# schema.net
KiCad netlist of a schematic drawn in Altium Designer
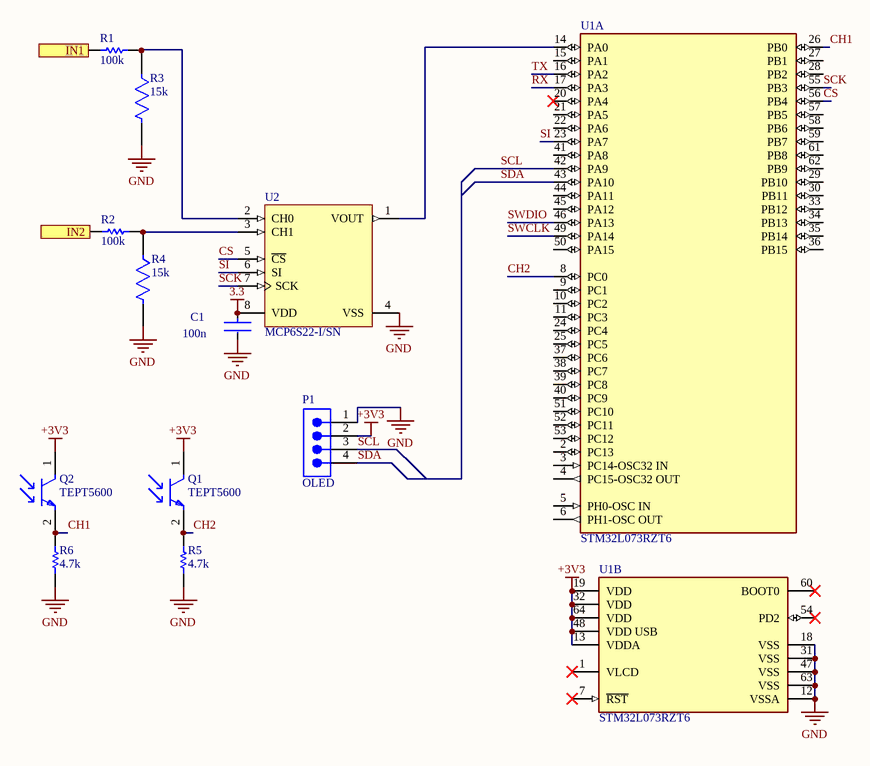
[diagram p0: schema.SchDoc]

(export (version "E")
  (design (tool "Eeschema 10.0.6"))
  (components
    (comp (ref "C1")
      (value "100n")
      (footprint "FP-0402B104K500CT-IPC_C")
      (description "CAP CER 0.1UF 50V X7R 0402")
      (fields (field (name "TOLERANCE") "10%"))
      (libsource (lib "Altium Content Vault") (part "11868f565c42a9108669ba33697ecf6"))
    )
    (comp (ref "P1")
      (value "OLED")
      (footprint "SMTC-MTSW-104-07-X-S-170")
      (fields (field (name "PARTNUMBER") "MTSW-104-07-T-S-170") (field (name "MANUFACTURER") "Samtec"))
      (libsource (lib "Altium Content Vault") (part "SMTC-MTSW-104-07-X-S-170"))
    )
    (comp (ref "Q1")
      (value "TEPT5600")
      (footprint "FP-6_544-5410_01-4-MFG")
      (description "VEMT2023SLX01 VEMT2023 Series 20 V 50 mA Silicon NPN Phototransistor - SMD-2")
      (libsource (lib "Altium Content Vault") (part "9aae5ca7057449e2492cc69ba8b14d6"))
    )
    (comp (ref "Q2")
      (value "TEPT5600")
      (footprint "FP-6_544-5410_01-4-MFG")
      (description "VEMT2023SLX01 VEMT2023 Series 20 V 50 mA Silicon NPN Phototransistor - SMD-2")
      (libsource (lib "Altium Content Vault") (part "9aae5ca7057449e2492cc69ba8b14d6"))
    )
    (comp (ref "R1")
      (value "100k")
      (footprint "RESC1005X40X25ML10T10")
      (fields (field (name "PART NUMBER") "SG73P1ETTP1003F") (field (name "MANUFACTURER") "KOA Speer"))
      (libsource (lib "Altium Content Vault") (part "RES"))
    )
    (comp (ref "R2")
      (value "100k")
      (footprint "RESC1005X40X25ML10T10")
      (fields (field (name "PART NUMBER") "SG73P1ETTP1003F") (field (name "MANUFACTURER") "KOA Speer"))
      (libsource (lib "Altium Content Vault") (part "RES"))
    )
    (comp (ref "R3")
      (value "15k")
      (footprint "FP-CRGP0603-IPC_C")
      (description "CRGP0603 15KΩ 0.25W ±100ppm/°C 1% 50V")
      (fields (field (name "MANUFACTURER") "TE") (field (name "MANUFACTURER PART NUMBER") "CRGP0603F15K"))
      (libsource (lib "Altium Content Vault") (part "1029c3af85768c4190bb7ad29bc67b5"))
    )
    (comp (ref "R4")
      (value "15k")
      (footprint "FP-CRGP0603-IPC_C")
      (description "CRGP0603 15KΩ 0.25W ±100ppm/°C 1% 50V")
      (fields (field (name "MANUFACTURER") "TE") (field (name "MANUFACTURER PART NUMBER") "CRGP0603F15K"))
      (libsource (lib "Altium Content Vault") (part "1029c3af85768c4190bb7ad29bc67b5"))
    )
    (comp (ref "R5")
      (value "4.7k")
      (footprint "RESC2512(6432)_N")
      (description "825R 1W 1% 2512 (6432 Metric)  SMD")
      (fields (field (name "POWER") "1 W") (field (name "TOLERANCE") "1 %"))
      (libsource (lib "Altium Content Vault") (part "RES"))
    )
    (comp (ref "R6")
      (value "4.7k")
      (footprint "RESC2512(6432)_N")
      (description "825R 1W 1% 2512 (6432 Metric)  SMD")
      (fields (field (name "POWER") "1 W") (field (name "TOLERANCE") "1 %"))
      (libsource (lib "Altium Content Vault") (part "RES"))
    )
    (comp (ref "U1")
      (value "STM32L073RZT6")
      (footprint "FP-LQFP64-5W-MFG")
      (description "IC MCU 32BIT 192KB FLASH 64LQFP")
      (libsource (lib "Altium Content Vault") (part "4466eda20ed5015702b21cb01f06cb7"))
    )
    (comp (ref "U2")
      (value "MCP6S22-I/SN")
      (footprint "SOIC-SN8_M")
      (libsource (lib "Altium Content Vault") (part "AMP-VGA-MCP6S22-IL8"))
    )
  )
  (nets
    (net (code "1") (name "+3V3") (class "Default")
      (node (ref "P1") (pin "2") (pinfunction "2_2") (pintype "passive"))
      (node (ref "Q1") (pin "1") (pinfunction "C_1") (pintype "passive"))
      (node (ref "Q2") (pin "1") (pinfunction "C_1") (pintype "passive"))
      (node (ref "U1") (pin "13") (pinfunction "VDDA_13") (pintype "power_in"))
      (node (ref "U1") (pin "19") (pinfunction "VDD_19") (pintype "power_in"))
      (node (ref "U1") (pin "32") (pinfunction "VDD_32") (pintype "power_in"))
      (node (ref "U1") (pin "48") (pinfunction "VDD_USB_48") (pintype "power_in"))
      (node (ref "U1") (pin "64") (pinfunction "VDD_64") (pintype "power_in"))
    )
    (net (code "2") (name "/CH1") (class "Default")
      (node (ref "Q2") (pin "2") (pinfunction "E_2") (pintype "passive"))
      (node (ref "R6") (pin "2") (pinfunction "2_2") (pintype "passive"))
      (node (ref "U1") (pin "26") (pinfunction "PB0_26") (pintype "bidirectional"))
    )
    (net (code "3") (name "/CH2") (class "Default")
      (node (ref "Q1") (pin "2") (pinfunction "E_2") (pintype "passive"))
      (node (ref "R5") (pin "2") (pinfunction "2_2") (pintype "passive"))
      (node (ref "U1") (pin "8") (pinfunction "PC0_8") (pintype "bidirectional"))
    )
    (net (code "4") (name "/CS") (class "Default")
      (node (ref "U1") (pin "56") (pinfunction "PB4_56") (pintype "bidirectional"))
      (node (ref "U2") (pin "5") (pinfunction "~{CS}_5") (pintype "input"))
    )
    (net (code "7") (name "/RX") (class "Default")
      (node (ref "U1") (pin "17") (pinfunction "PA3_17") (pintype "bidirectional"))
    )
    (net (code "8") (name "/SCK") (class "Default")
      (node (ref "U1") (pin "55") (pinfunction "PB3_55") (pintype "bidirectional"))
      (node (ref "U2") (pin "7") (pinfunction "SCK_7") (pintype "input"))
    )
    (net (code "9") (name "/SCL") (class "Default")
      (node (ref "P1") (pin "3") (pinfunction "3_3") (pintype "passive"))
      (node (ref "U1") (pin "42") (pinfunction "PA9_42") (pintype "bidirectional"))
    )
    (net (code "10") (name "/SDA") (class "Default")
      (node (ref "P1") (pin "4") (pinfunction "4_4") (pintype "passive"))
      (node (ref "U1") (pin "43") (pinfunction "PA10_43") (pintype "bidirectional"))
    )
    (net (code "11") (name "/SI") (class "Default")
      (node (ref "U1") (pin "23") (pinfunction "PA7_23") (pintype "bidirectional"))
      (node (ref "U2") (pin "6") (pinfunction "SI_6") (pintype "input"))
    )
    (net (code "12") (name "/SWCLK") (class "Default")
      (node (ref "U1") (pin "49") (pinfunction "PA14_49") (pintype "bidirectional"))
    )
    (net (code "13") (name "/SWDIO") (class "Default")
      (node (ref "U1") (pin "46") (pinfunction "PA13_46") (pintype "bidirectional"))
    )
    (net (code "14") (name "/TX") (class "Default")
      (node (ref "U1") (pin "16") (pinfunction "PA2_16") (pintype "bidirectional"))
    )
    (net (code "15") (name "3.3") (class "Default")
      (node (ref "C1") (pin "1") (pinfunction "1_1") (pintype "passive"))
      (node (ref "U2") (pin "8") (pinfunction "VDD_8") (pintype "power_in"))
    )
    (net (code "16") (name "GND") (class "Default")
      (node (ref "C1") (pin "2") (pinfunction "2_2") (pintype "passive"))
      (node (ref "P1") (pin "1") (pinfunction "1_1") (pintype "passive"))
      (node (ref "R3") (pin "2") (pinfunction "2_2") (pintype "passive"))
      (node (ref "R4") (pin "2") (pinfunction "2_2") (pintype "passive"))
      (node (ref "R5") (pin "1") (pinfunction "1_1") (pintype "passive"))
      (node (ref "R6") (pin "1") (pinfunction "1_1") (pintype "passive"))
      (node (ref "U1") (pin "12") (pinfunction "VSSA_12") (pintype "power_in"))
      (node (ref "U1") (pin "18") (pinfunction "VSS_18") (pintype "power_in"))
      (node (ref "U1") (pin "31") (pinfunction "VSS_31") (pintype "power_in"))
      (node (ref "U1") (pin "47") (pinfunction "VSS_47") (pintype "power_in"))
      (node (ref "U1") (pin "63") (pinfunction "VSS_63") (pintype "power_in"))
      (node (ref "U2") (pin "4") (pinfunction "VSS_4") (pintype "power_in"))
    )
    (net (code "17") (name "Net-(U1A-PA0)") (class "Default")
      (node (ref "U1") (pin "14") (pinfunction "PA0_14") (pintype "bidirectional"))
      (node (ref "U2") (pin "1") (pinfunction "VOUT_1") (pintype "output"))
    )
    (net (code "18") (name "Net-(U2-CH0)") (class "Default")
      (node (ref "R1") (pin "2") (pinfunction "2_2") (pintype "passive"))
      (node (ref "R3") (pin "1") (pinfunction "1_1") (pintype "passive"))
      (node (ref "U2") (pin "2") (pinfunction "CH0_2") (pintype "input"))
    )
    (net (code "19") (name "Net-(U2-CH1)") (class "Default")
      (node (ref "R2") (pin "2") (pinfunction "2_2") (pintype "passive"))
      (node (ref "R4") (pin "1") (pinfunction "1_1") (pintype "passive"))
      (node (ref "U2") (pin "3") (pinfunction "CH1_3") (pintype "input"))
    )
    (net (code "20") (name "unconnected-(R1-Pad1)") (class "Default")
      (node (ref "R1") (pin "1") (pinfunction "1_1") (pintype "passive"))
    )
    (net (code "21") (name "unconnected-(R2-Pad1)") (class "Default")
      (node (ref "R2") (pin "1") (pinfunction "1_1") (pintype "passive"))
    )
    (net (code "22") (name "unconnected-(U1A-PA1-Pad15)") (class "Default")
      (node (ref "U1") (pin "15") (pinfunction "PA1_15") (pintype "bidirectional"))
    )
    (net (code "23") (name "unconnected-(U1A-PA4-Pad20)") (class "Default")
      (node (ref "U1") (pin "20") (pinfunction "PA4_20") (pintype "bidirectional+no_connect"))
    )
    (net (code "24") (name "unconnected-(U1A-PA5-Pad21)") (class "Default")
      (node (ref "U1") (pin "21") (pinfunction "PA5_21") (pintype "bidirectional"))
    )
    (net (code "25") (name "unconnected-(U1A-PA6-Pad22)") (class "Default")
      (node (ref "U1") (pin "22") (pinfunction "PA6_22") (pintype "bidirectional"))
    )
    (net (code "26") (name "unconnected-(U1A-PA8-Pad41)") (class "Default")
      (node (ref "U1") (pin "41") (pinfunction "PA8_41") (pintype "bidirectional"))
    )
    (net (code "27") (name "unconnected-(U1A-PA11-Pad44)") (class "Default")
      (node (ref "U1") (pin "44") (pinfunction "PA11_44") (pintype "bidirectional"))
    )
    (net (code "28") (name "unconnected-(U1A-PA12-Pad45)") (class "Default")
      (node (ref "U1") (pin "45") (pinfunction "PA12_45") (pintype "bidirectional"))
    )
    (net (code "29") (name "unconnected-(U1A-PA15-Pad50)") (class "Default")
      (node (ref "U1") (pin "50") (pinfunction "PA15_50") (pintype "bidirectional"))
    )
    (net (code "30") (name "unconnected-(U1A-PB1-Pad27)") (class "Default")
      (node (ref "U1") (pin "27") (pinfunction "PB1_27") (pintype "bidirectional"))
    )
    (net (code "31") (name "unconnected-(U1A-PB2-Pad28)") (class "Default")
      (node (ref "U1") (pin "28") (pinfunction "PB2_28") (pintype "bidirectional"))
    )
    (net (code "32") (name "unconnected-(U1A-PB5-Pad57)") (class "Default")
      (node (ref "U1") (pin "57") (pinfunction "PB5_57") (pintype "bidirectional"))
    )
    (net (code "33") (name "unconnected-(U1A-PB6-Pad58)") (class "Default")
      (node (ref "U1") (pin "58") (pinfunction "PB6_58") (pintype "bidirectional"))
    )
    (net (code "34") (name "unconnected-(U1A-PB7-Pad59)") (class "Default")
      (node (ref "U1") (pin "59") (pinfunction "PB7_59") (pintype "bidirectional"))
    )
    (net (code "35") (name "unconnected-(U1A-PB8-Pad61)") (class "Default")
      (node (ref "U1") (pin "61") (pinfunction "PB8_61") (pintype "bidirectional"))
    )
    (net (code "36") (name "unconnected-(U1A-PB9-Pad62)") (class "Default")
      (node (ref "U1") (pin "62") (pinfunction "PB9_62") (pintype "bidirectional"))
    )
    (net (code "37") (name "unconnected-(U1A-PB10-Pad29)") (class "Default")
      (node (ref "U1") (pin "29") (pinfunction "PB10_29") (pintype "bidirectional"))
    )
    (net (code "38") (name "unconnected-(U1A-PB11-Pad30)") (class "Default")
      (node (ref "U1") (pin "30") (pinfunction "PB11_30") (pintype "bidirectional"))
    )
    (net (code "39") (name "unconnected-(U1A-PB12-Pad33)") (class "Default")
      (node (ref "U1") (pin "33") (pinfunction "PB12_33") (pintype "bidirectional"))
    )
    (net (code "40") (name "unconnected-(U1A-PB13-Pad34)") (class "Default")
      (node (ref "U1") (pin "34") (pinfunction "PB13_34") (pintype "bidirectional"))
    )
    (net (code "41") (name "unconnected-(U1A-PB14-Pad35)") (class "Default")
      (node (ref "U1") (pin "35") (pinfunction "PB14_35") (pintype "bidirectional"))
    )
    (net (code "42") (name "unconnected-(U1A-PB15-Pad36)") (class "Default")
      (node (ref "U1") (pin "36") (pinfunction "PB15_36") (pintype "bidirectional"))
    )
    (net (code "43") (name "unconnected-(U1A-PC1-Pad9)") (class "Default")
      (node (ref "U1") (pin "9") (pinfunction "PC1_9") (pintype "bidirectional"))
    )
    (net (code "44") (name "unconnected-(U1A-PC2-Pad10)") (class "Default")
      (node (ref "U1") (pin "10") (pinfunction "PC2_10") (pintype "bidirectional"))
    )
    (net (code "45") (name "unconnected-(U1A-PC3-Pad11)") (class "Default")
      (node (ref "U1") (pin "11") (pinfunction "PC3_11") (pintype "bidirectional"))
    )
    (net (code "46") (name "unconnected-(U1A-PC4-Pad24)") (class "Default")
      (node (ref "U1") (pin "24") (pinfunction "PC4_24") (pintype "bidirectional"))
    )
    (net (code "47") (name "unconnected-(U1A-PC5-Pad25)") (class "Default")
      (node (ref "U1") (pin "25") (pinfunction "PC5_25") (pintype "bidirectional"))
    )
    (net (code "48") (name "unconnected-(U1A-PC6-Pad37)") (class "Default")
      (node (ref "U1") (pin "37") (pinfunction "PC6_37") (pintype "bidirectional"))
    )
    (net (code "49") (name "unconnected-(U1A-PC7-Pad38)") (class "Default")
      (node (ref "U1") (pin "38") (pinfunction "PC7_38") (pintype "bidirectional"))
    )
    (net (code "50") (name "unconnected-(U1A-PC8-Pad39)") (class "Default")
      (node (ref "U1") (pin "39") (pinfunction "PC8_39") (pintype "bidirectional"))
    )
    (net (code "51") (name "unconnected-(U1A-PC9-Pad40)") (class "Default")
      (node (ref "U1") (pin "40") (pinfunction "PC9_40") (pintype "bidirectional"))
    )
    (net (code "52") (name "unconnected-(U1A-PC10-Pad51)") (class "Default")
      (node (ref "U1") (pin "51") (pinfunction "PC10_51") (pintype "bidirectional"))
    )
    (net (code "53") (name "unconnected-(U1A-PC11-Pad52)") (class "Default")
      (node (ref "U1") (pin "52") (pinfunction "PC11_52") (pintype "bidirectional"))
    )
    (net (code "54") (name "unconnected-(U1A-PC12-Pad53)") (class "Default")
      (node (ref "U1") (pin "53") (pinfunction "PC12_53") (pintype "bidirectional"))
    )
    (net (code "55") (name "unconnected-(U1A-PC13-Pad2)") (class "Default")
      (node (ref "U1") (pin "2") (pinfunction "PC13_2") (pintype "bidirectional"))
    )
    (net (code "56") (name "unconnected-(U1A-PC14-OSC32_IN-Pad3)") (class "Default")
      (node (ref "U1") (pin "3") (pinfunction "PC14-OSC32_IN_3") (pintype "input"))
    )
    (net (code "57") (name "unconnected-(U1A-PC15-OSC32_OUT-Pad4)") (class "Default")
      (node (ref "U1") (pin "4") (pinfunction "PC15-OSC32_OUT_4") (pintype "output"))
    )
    (net (code "58") (name "unconnected-(U1A-PH0-OSC_IN-Pad5)") (class "Default")
      (node (ref "U1") (pin "5") (pinfunction "PH0-OSC_IN_5") (pintype "input"))
    )
    (net (code "59") (name "unconnected-(U1A-PH1-OSC_OUT-Pad6)") (class "Default")
      (node (ref "U1") (pin "6") (pinfunction "PH1-OSC_OUT_6") (pintype "output"))
    )
    (net (code "60") (name "unconnected-(U1B-BOOT0-Pad60)") (class "Default")
      (node (ref "U1") (pin "60") (pinfunction "BOOT0_60") (pintype "passive+no_connect"))
    )
    (net (code "61") (name "unconnected-(U1B-PD2-Pad54)") (class "Default")
      (node (ref "U1") (pin "54") (pinfunction "PD2_54") (pintype "bidirectional+no_connect"))
    )
    (net (code "62") (name "unconnected-(U1B-VLCD-Pad1)") (class "Default")
      (node (ref "U1") (pin "1") (pinfunction "VLCD_1") (pintype "power_in+no_connect"))
    )
    (net (code "63") (name "unconnected-(U1B-~{RST}-Pad7)") (class "Default")
      (node (ref "U1") (pin "7") (pinfunction "~{RST}_7") (pintype "input+no_connect"))
    )
  )
)
